# top.net
KiCad netlist of a schematic drawn in Altium Designer
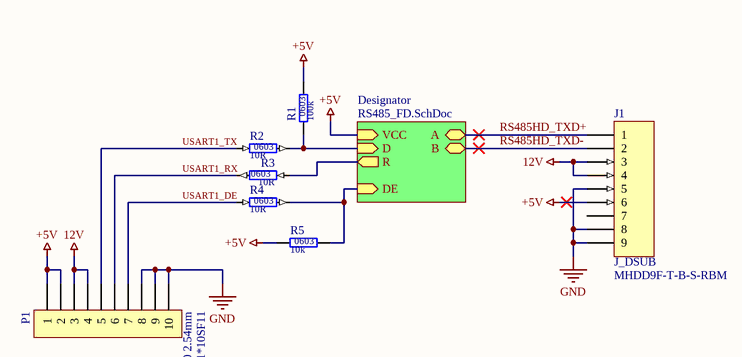
[diagram p0: top.SchDoc]

(export (version "E")
  (design (tool "Eeschema 10.0.6"))
  (components
    (comp (ref "J1")
      (value "MHDD9F-T-B-S-RBM")
      (footprint "J_DSUB_MHDD9F-T-B-S-RBM")
      (description "Header, 9-Pin")
      (fields
        (field (name "SCH_FOOTPRINT") "J_DSUB")
        (field (name "PART NUMBER") "J_DSUB")
        (field (name "Comment") "DSUB 9 Pin")
      )
      (libsource (lib "Library") (part "J_DSUB"))
    )
    (comp (ref "P1")
      (value "DS1021-1*10SF11")
      (footprint "P_HEADER_1x10_2.54")
      (description "Pin Header")
      (fields
        (field (name "SCH_FOOTPRINT") "1x10 2.54mm")
        (field (name "PART NUMBER") "P_HEADER_1x10_2.54")
        (field (name "MANUFACTURER") "Connfly")
      )
      (libsource (lib "Library") (part "P_HEADER_1x10"))
    )
    (comp (ref "R1")
      (value "100k")
      (footprint "R_0603_1608")
      (fields
        (field (name "SCH_FOOTPRINT") "0603")
        (field (name "PART NUMBER") "R_100k_0603_1")
        (field (name "VOLTAGE") "50V")
        (field (name "POWER") "100mW")
      )
      (libsource (lib "") (part "R_1"))
    )
    (comp (ref "R2")
      (value "10R")
      (footprint "R_0603_1608")
      (fields
        (field (name "SCH_FOOTPRINT") "0603")
        (field (name "PART NUMBER") "R_10R_0603_1")
        (field (name "VOLTAGE") "50V")
        (field (name "POWER") "100mW")
      )
      (libsource (lib "Library") (part "R"))
    )
    (comp (ref "R3")
      (value "10R")
      (footprint "R_0603_1608")
      (fields
        (field (name "SCH_FOOTPRINT") "0603")
        (field (name "PART NUMBER") "R_10R_0603_1")
        (field (name "VOLTAGE") "50V")
        (field (name "POWER") "100mW")
      )
      (libsource (lib "Library") (part "R"))
    )
    (comp (ref "R4")
      (value "10R")
      (footprint "R_0603_1608")
      (fields
        (field (name "SCH_FOOTPRINT") "0603")
        (field (name "PART NUMBER") "R_10R_0603_1")
        (field (name "VOLTAGE") "50V")
        (field (name "POWER") "100mW")
      )
      (libsource (lib "Library") (part "R"))
    )
    (comp (ref "R5")
      (value "10k")
      (footprint "R_0603_1608")
      (fields
        (field (name "SCH_FOOTPRINT") "0603")
        (field (name "PART NUMBER") "R_10k_0603_1")
        (field (name "VOLTAGE") "75V")
        (field (name "POWER") "100mW")
      )
      (libsource (lib "") (part "R_1"))
    )
  )
  (nets
    (net (code "1") (name "+5V") (class "Default")
      (node (ref "J1") (pin "6") (pinfunction "6_6") (pintype "input"))
      (node (ref "P1") (pin "1") (pinfunction "1_1") (pintype "passive"))
      (node (ref "P1") (pin "2") (pinfunction "2_2") (pintype "passive"))
      (node (ref "R1") (pin "2") (pinfunction "2_2") (pintype "passive"))
      (node (ref "R5") (pin "1") (pinfunction "1_1") (pintype "passive"))
    )
    (net (code "2") (name "/D") (class "Default")
      (node (ref "R1") (pin "1") (pinfunction "1_1") (pintype "passive"))
      (node (ref "R2") (pin "2") (pinfunction "2_2") (pintype "output"))
    )
    (net (code "3") (name "/DE") (class "Default")
      (node (ref "R4") (pin "2") (pinfunction "2_2") (pintype "output"))
      (node (ref "R5") (pin "2") (pinfunction "2_2") (pintype "passive"))
    )
    (net (code "4") (name "/R") (class "Default")
      (node (ref "R3") (pin "1") (pinfunction "1_1") (pintype "input"))
    )
    (net (code "5") (name "/RS485HD_TXD+") (class "Default")
      (node (ref "J1") (pin "1") (pinfunction "1_1") (pintype "passive"))
    )
    (net (code "6") (name "/RS485HD_TXD-") (class "Default")
      (node (ref "J1") (pin "2") (pinfunction "2_2") (pintype "passive"))
    )
    (net (code "7") (name "/USART1_DE") (class "Default")
      (node (ref "P1") (pin "7") (pinfunction "7_7") (pintype "passive"))
      (node (ref "R4") (pin "1") (pinfunction "1_1") (pintype "input"))
    )
    (net (code "8") (name "/USART1_RX") (class "Default")
      (node (ref "P1") (pin "6") (pinfunction "6_6") (pintype "passive"))
      (node (ref "R3") (pin "2") (pinfunction "2_2") (pintype "output"))
    )
    (net (code "9") (name "/USART1_TX") (class "Default")
      (node (ref "P1") (pin "5") (pinfunction "5_5") (pintype "passive"))
      (node (ref "R2") (pin "1") (pinfunction "1_1") (pintype "input"))
    )
    (net (code "10") (name "12V") (class "Default")
      (node (ref "J1") (pin "3") (pinfunction "3_3") (pintype "input"))
      (node (ref "J1") (pin "4") (pinfunction "4_4") (pintype "input"))
      (node (ref "P1") (pin "3") (pinfunction "3_3") (pintype "passive"))
      (node (ref "P1") (pin "4") (pinfunction "4_4") (pintype "passive"))
    )
    (net (code "11") (name "GND") (class "Default")
      (node (ref "J1") (pin "5") (pinfunction "5_5") (pintype "input"))
      (node (ref "J1") (pin "8") (pinfunction "8_8") (pintype "passive"))
      (node (ref "J1") (pin "9") (pinfunction "9_9") (pintype "passive"))
      (node (ref "P1") (pin "10") (pinfunction "10_10") (pintype "passive"))
      (node (ref "P1") (pin "8") (pinfunction "8_8") (pintype "passive"))
      (node (ref "P1") (pin "9") (pinfunction "9_9") (pintype "passive"))
    )
    (net (code "12") (name "unconnected-(J1-NC-Pad0)") (class "Default")
      (node (ref "J1") (pin "0") (pinfunction "NC_0") (pintype "passive"))
    )
    (net (code "13") (name "unconnected-(J1-Pad7)") (class "Default")
      (node (ref "J1") (pin "7") (pinfunction "7_7") (pintype "passive"))
    )
  )
)
